# Cargador_RasPi3HAT_CamSlot_v1_0.net
KiCad netlist of a schematic drawn in EAGLE
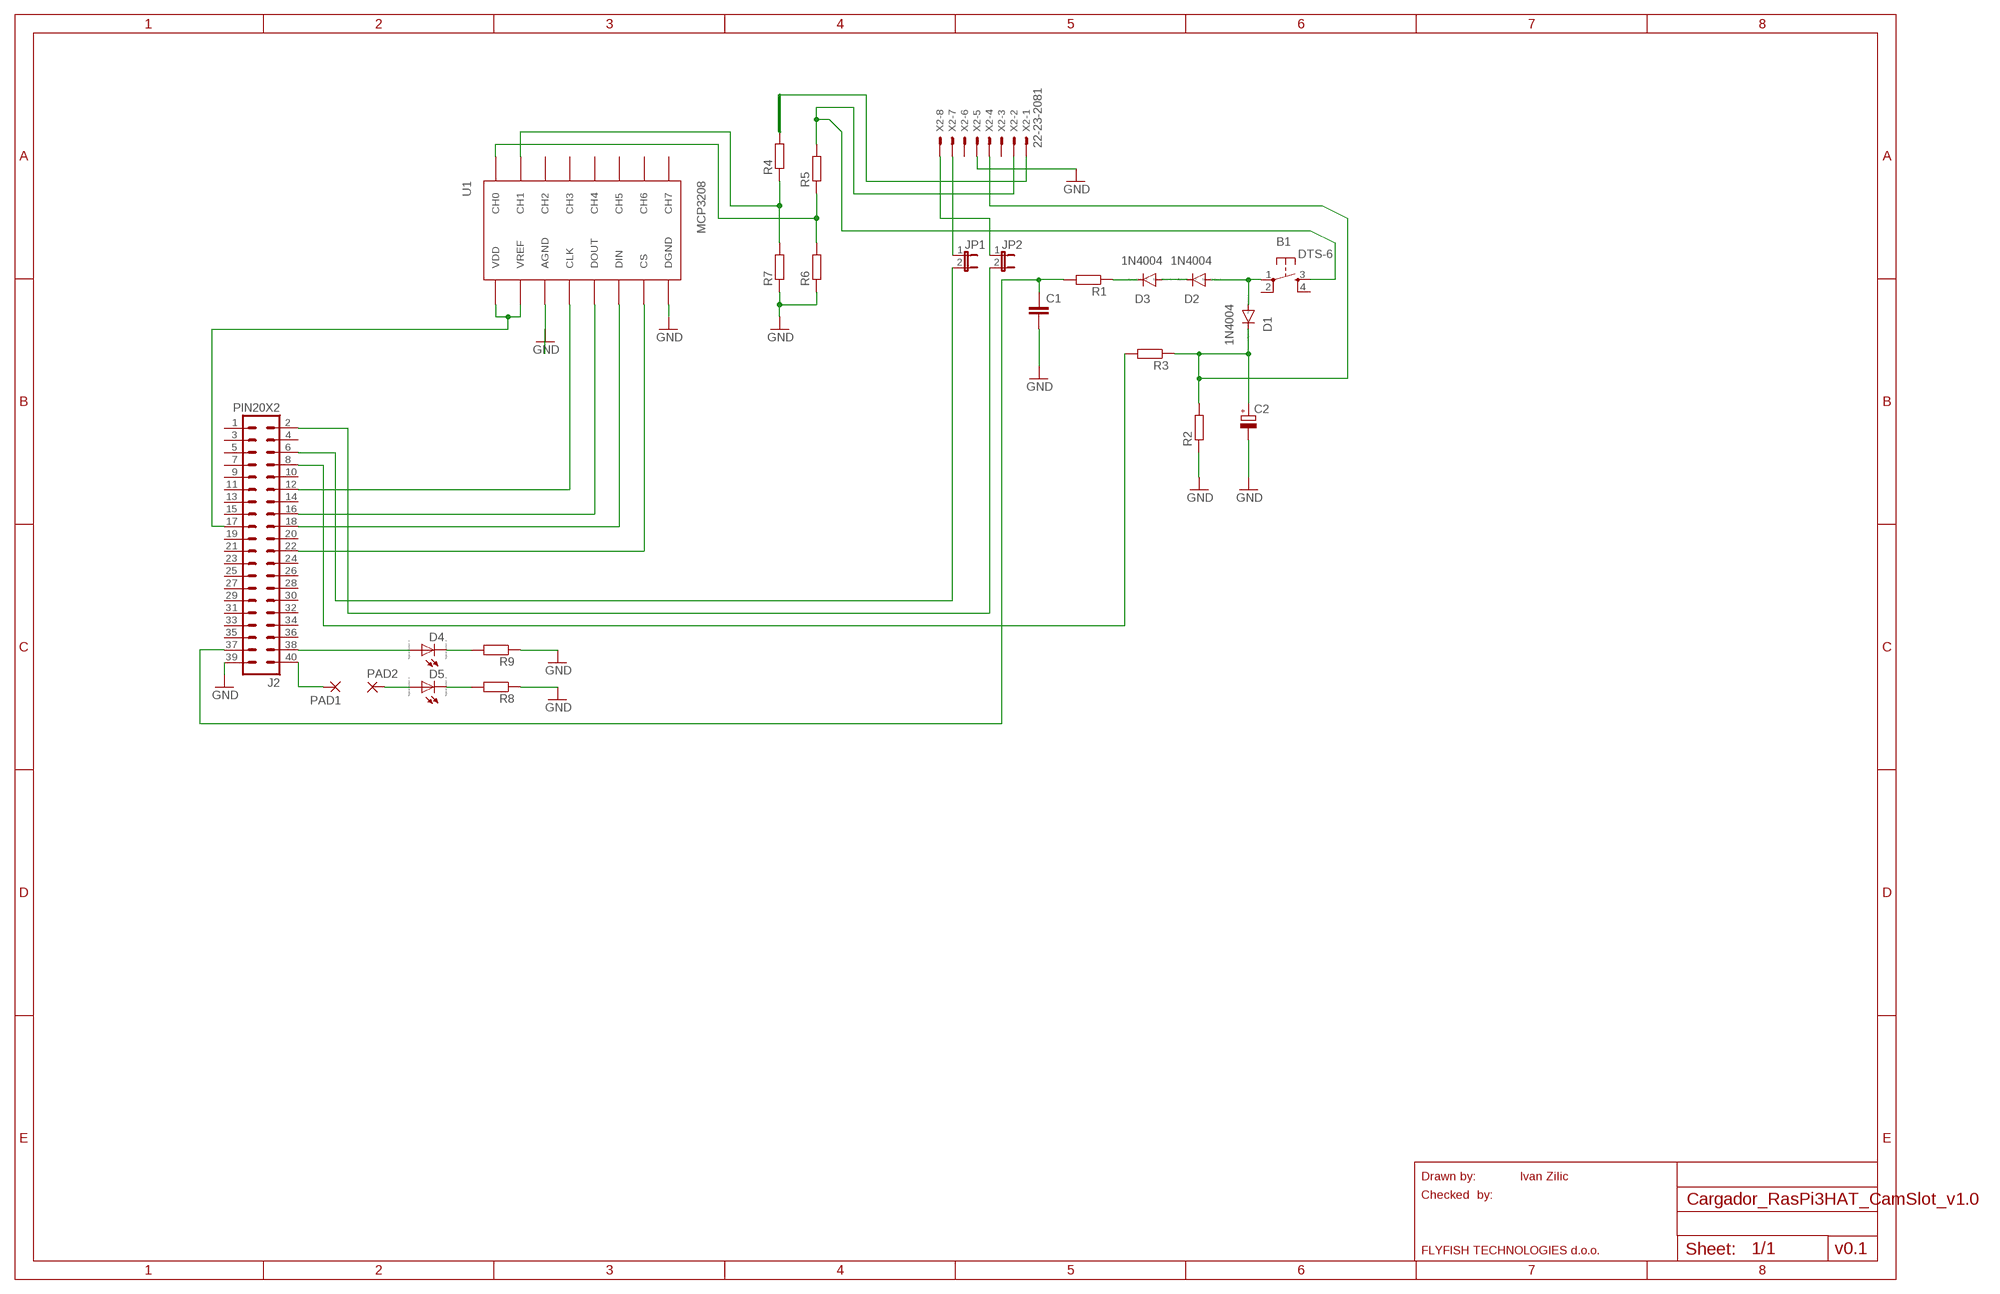
[diagram p0: schematic, sheet 1]

(export (version "E")
  (design (tool "Eeschema 10.0.6"))
  (components
    (comp (ref "B1")
      (value "DTS-6")
      (footprint "eagle-import:DTS-6")
      (libsource (lib "eagle-import") (part "DTS-6"))
    )
    (comp (ref "C1")
      (value "C2.5/2")
      (footprint "eagle-import:C2.5-2")
      (libsource (lib "eagle-import") (part "C2.5/2"))
    )
    (comp (ref "C2")
      (value "CPOL-EUE5-4")
      (footprint "eagle-import:E5-4")
      (libsource (lib "eagle-import") (part "CPOL-EUE5-4"))
    )
    (comp (ref "D1")
      (value "1N4004")
      (footprint "eagle-import:DO41-10")
      (libsource (lib "eagle-import") (part "1N4004"))
    )
    (comp (ref "D2")
      (value "1N4004")
      (footprint "eagle-import:DO41-10")
      (libsource (lib "eagle-import") (part "1N4004"))
    )
    (comp (ref "D3")
      (value "1N4004")
      (footprint "eagle-import:DO41-10")
      (libsource (lib "eagle-import") (part "1N4004"))
    )
    (comp (ref "D4")
      (value "LED_ELD260")
      (footprint "eagle-import:LED_LD260")
      (libsource (lib "eagle-import") (part "LED_ELD260"))
    )
    (comp (ref "D5")
      (value "LED_ELD260")
      (footprint "eagle-import:LED_LD260")
      (libsource (lib "eagle-import") (part "LED_ELD260"))
    )
    (comp (ref "J2")
      (value "PIN20X2")
      (footprint "eagle-import:PIN_20X2")
      (libsource (lib "eagle-import") (part "PIN20X2"))
    )
    (comp (ref "JP1")
      (value "JP1E")
      (footprint "eagle-import:JP1")
      (libsource (lib "eagle-import") (part "JP1E"))
    )
    (comp (ref "JP2")
      (value "JP1E")
      (footprint "eagle-import:JP1")
      (libsource (lib "eagle-import") (part "JP1E"))
    )
    (comp (ref "PAD1")
      (value "2,15/1,0")
      (footprint "eagle-import:2,15_1,0")
      (libsource (lib "eagle-import") (part "2,15/1,0"))
    )
    (comp (ref "PAD2")
      (value "2,15/1,0")
      (footprint "eagle-import:2,15_1,0")
      (libsource (lib "eagle-import") (part "2,15/1,0"))
    )
    (comp (ref "R1")
      (value "R-EU_0207/10")
      (footprint "eagle-import:0207_10")
      (libsource (lib "eagle-import") (part "R-EU_0207/10"))
    )
    (comp (ref "R2")
      (value "R-EU_0207/10")
      (footprint "eagle-import:0207_10")
      (libsource (lib "eagle-import") (part "R-EU_0207/10"))
    )
    (comp (ref "R3")
      (value "R-EU_0207/10")
      (footprint "eagle-import:0207_10")
      (libsource (lib "eagle-import") (part "R-EU_0207/10"))
    )
    (comp (ref "R4")
      (value "R-EU_0207/10")
      (footprint "eagle-import:0207_10")
      (libsource (lib "eagle-import") (part "R-EU_0207/10"))
    )
    (comp (ref "R5")
      (value "R-EU_0207/10")
      (footprint "eagle-import:0207_10")
      (libsource (lib "eagle-import") (part "R-EU_0207/10"))
    )
    (comp (ref "R6")
      (value "R-EU_0207/10")
      (footprint "eagle-import:0207_10")
      (libsource (lib "eagle-import") (part "R-EU_0207/10"))
    )
    (comp (ref "R7")
      (value "R-EU_0207/10")
      (footprint "eagle-import:0207_10")
      (libsource (lib "eagle-import") (part "R-EU_0207/10"))
    )
    (comp (ref "R8")
      (value "R-EU_0207/10")
      (footprint "eagle-import:0207_10")
      (libsource (lib "eagle-import") (part "R-EU_0207/10"))
    )
    (comp (ref "R9")
      (value "R-EU_0207/10")
      (footprint "eagle-import:0207_10")
      (libsource (lib "eagle-import") (part "R-EU_0207/10"))
    )
    (comp (ref "U1")
      (value "MCP3208")
      (footprint "eagle-import:DIL16")
      (libsource (lib "eagle-import") (part "MCP3208"))
    )
    (comp (ref "X2")
      (value "22-23-2081")
      (footprint "eagle-import:22-23-2081")
      (fields (field (name "MF") "MOLEX"))
      (libsource (lib "eagle-import") (part "22-23-2081"))
    )
  )
  (nets
    (net (code "1") (name "GND") (class "Default")
      (node (ref "C1") (pin "2") (pinfunction "2_2") (pintype "passive"))
      (node (ref "C2") (pin "-") (pinfunction "-_-") (pintype "passive"))
      (node (ref "J2") (pin "39") (pinfunction "39_39") (pintype "passive"))
      (node (ref "R2") (pin "1") (pinfunction "1_1") (pintype "passive"))
      (node (ref "R6") (pin "1") (pinfunction "1_1") (pintype "passive"))
      (node (ref "R7") (pin "1") (pinfunction "1_1") (pintype "passive"))
      (node (ref "R8") (pin "1") (pinfunction "1_1") (pintype "passive"))
      (node (ref "R9") (pin "1") (pinfunction "1_1") (pintype "passive"))
      (node (ref "U1") (pin "AGND") (pinfunction "AGND_AGND") (pintype "power_in"))
      (node (ref "U1") (pin "DGND") (pinfunction "DGND_DGND") (pintype "power_in"))
      (node (ref "X2") (pin "5") (pinfunction "S_5") (pintype "passive"))
    )
    (net (code "2") (name "Net-(B1-Pad1)") (class "Default")
      (node (ref "B1") (pin "1") (pinfunction "1_1") (pintype "passive"))
      (node (ref "D1") (pin "A") (pinfunction "A_A") (pintype "passive"))
      (node (ref "D2") (pin "A") (pinfunction "A_A") (pintype "passive"))
    )
    (net (code "3") (name "Net-(C1-Pad1)") (class "Default")
      (node (ref "C1") (pin "1") (pinfunction "1_1") (pintype "passive"))
      (node (ref "J2") (pin "37") (pinfunction "37_37") (pintype "passive"))
      (node (ref "R1") (pin "2") (pinfunction "2_2") (pintype "passive"))
    )
    (net (code "4") (name "Net-(D2-PadC)") (class "Default")
      (node (ref "D2") (pin "C") (pinfunction "C_C") (pintype "passive"))
      (node (ref "D3") (pin "A") (pinfunction "A_A") (pintype "passive"))
    )
    (net (code "5") (name "Net-(D3-PadC)") (class "Default")
      (node (ref "D3") (pin "C") (pinfunction "C_C") (pintype "passive"))
      (node (ref "R1") (pin "1") (pinfunction "1_1") (pintype "passive"))
    )
    (net (code "6") (name "Net-(D4-C)") (class "Default")
      (node (ref "D4") (pin "K") (pinfunction "C_K") (pintype "passive"))
      (node (ref "R9") (pin "2") (pinfunction "2_2") (pintype "passive"))
    )
    (net (code "7") (name "Net-(D4-PadA)") (class "Default")
      (node (ref "D4") (pin "A") (pinfunction "A_A") (pintype "passive"))
      (node (ref "J2") (pin "38") (pinfunction "38_38") (pintype "passive"))
    )
    (net (code "8") (name "Net-(D5-C)") (class "Default")
      (node (ref "D5") (pin "K") (pinfunction "C_K") (pintype "passive"))
      (node (ref "R8") (pin "2") (pinfunction "2_2") (pintype "passive"))
    )
    (net (code "9") (name "Net-(J2-Pad2)") (class "Default")
      (node (ref "J2") (pin "2") (pinfunction "2_2") (pintype "passive"))
      (node (ref "JP2") (pin "2") (pinfunction "2_2") (pintype "passive"))
    )
    (net (code "10") (name "Net-(J2-Pad6)") (class "Default")
      (node (ref "J2") (pin "6") (pinfunction "6_6") (pintype "passive"))
      (node (ref "JP1") (pin "2") (pinfunction "2_2") (pintype "passive"))
    )
    (net (code "11") (name "Net-(J2-Pad8)") (class "Default")
      (node (ref "J2") (pin "8") (pinfunction "8_8") (pintype "passive"))
      (node (ref "R3") (pin "2") (pinfunction "2_2") (pintype "passive"))
    )
    (net (code "12") (name "Net-(J2-Pad12)") (class "Default")
      (node (ref "J2") (pin "12") (pinfunction "12_12") (pintype "passive"))
      (node (ref "U1") (pin "CLK") (pinfunction "CLK_CLK") (pintype "input"))
    )
    (net (code "13") (name "Net-(J2-Pad16)") (class "Default")
      (node (ref "J2") (pin "16") (pinfunction "16_16") (pintype "passive"))
      (node (ref "U1") (pin "DOUT") (pinfunction "DOUT_DOUT") (pintype "output"))
    )
    (net (code "14") (name "Net-(J2-Pad17)") (class "Default")
      (node (ref "J2") (pin "17") (pinfunction "17_17") (pintype "passive"))
      (node (ref "U1") (pin "VDD") (pinfunction "VDD_VDD") (pintype "power_in"))
      (node (ref "U1") (pin "VREF") (pinfunction "VREF_VREF") (pintype "input"))
    )
    (net (code "15") (name "Net-(J2-Pad18)") (class "Default")
      (node (ref "J2") (pin "18") (pinfunction "18_18") (pintype "passive"))
      (node (ref "U1") (pin "DIN") (pinfunction "DIN_DIN") (pintype "input"))
    )
    (net (code "16") (name "Net-(J2-Pad22)") (class "Default")
      (node (ref "J2") (pin "22") (pinfunction "22_22") (pintype "passive"))
      (node (ref "U1") (pin "CS") (pinfunction "CS_CS") (pintype "input"))
    )
    (net (code "17") (name "Net-(PAD1-P)") (class "Default")
      (node (ref "J2") (pin "40") (pinfunction "40_40") (pintype "passive"))
      (node (ref "PAD1") (pin "1") (pinfunction "P_1") (pintype "passive"))
    )
    (net (code "18") (name "Net-(PAD2-P)") (class "Default")
      (node (ref "D5") (pin "A") (pinfunction "A_A") (pintype "passive"))
      (node (ref "PAD2") (pin "1") (pinfunction "P_1") (pintype "passive"))
    )
    (net (code "19") (name "Net-(R4-Pad1)") (class "Default")
      (node (ref "R4") (pin "1") (pinfunction "1_1") (pintype "passive"))
      (node (ref "R7") (pin "2") (pinfunction "2_2") (pintype "passive"))
      (node (ref "U1") (pin "CH1") (pinfunction "CH1_CH1") (pintype "input"))
    )
    (net (code "20") (name "Net-(R5-Pad1)") (class "Default")
      (node (ref "R5") (pin "1") (pinfunction "1_1") (pintype "passive"))
      (node (ref "R6") (pin "2") (pinfunction "2_2") (pintype "passive"))
      (node (ref "U1") (pin "CH0") (pinfunction "CH0_CH0") (pintype "input"))
    )
    (net (code "21") (name "Net-(X2A-S)") (class "Default")
      (node (ref "R4") (pin "2") (pinfunction "2_2") (pintype "passive"))
      (node (ref "X2") (pin "1") (pinfunction "S_1") (pintype "passive"))
    )
    (net (code "22") (name "Net-(X2B-S)") (class "Default")
      (node (ref "B1") (pin "3") (pinfunction "3_3") (pintype "passive"))
      (node (ref "R5") (pin "2") (pinfunction "2_2") (pintype "passive"))
      (node (ref "X2") (pin "2") (pinfunction "S_2") (pintype "passive"))
    )
    (net (code "23") (name "Net-(X2D-S)") (class "Default")
      (node (ref "C2") (pin "+") (pinfunction "+_+") (pintype "passive"))
      (node (ref "D1") (pin "C") (pinfunction "C_C") (pintype "passive"))
      (node (ref "R2") (pin "2") (pinfunction "2_2") (pintype "passive"))
      (node (ref "R3") (pin "1") (pinfunction "1_1") (pintype "passive"))
      (node (ref "X2") (pin "4") (pinfunction "S_4") (pintype "passive"))
    )
    (net (code "24") (name "Net-(X2G-S)") (class "Default")
      (node (ref "JP1") (pin "1") (pinfunction "1_1") (pintype "passive"))
      (node (ref "X2") (pin "7") (pinfunction "S_7") (pintype "passive"))
    )
    (net (code "25") (name "Net-(X2H-S)") (class "Default")
      (node (ref "JP2") (pin "1") (pinfunction "1_1") (pintype "passive"))
      (node (ref "X2") (pin "8") (pinfunction "S_8") (pintype "passive"))
    )
    (net (code "26") (name "unconnected-(B1-Pad2)") (class "Default")
      (node (ref "B1") (pin "2") (pinfunction "2_2") (pintype "passive"))
    )
    (net (code "27") (name "unconnected-(B1-Pad4)") (class "Default")
      (node (ref "B1") (pin "4") (pinfunction "4_4") (pintype "passive"))
    )
    (net (code "28") (name "unconnected-(J2-Pad1)") (class "Default")
      (node (ref "J2") (pin "1") (pinfunction "1_1") (pintype "passive"))
    )
    (net (code "29") (name "unconnected-(J2-Pad3)") (class "Default")
      (node (ref "J2") (pin "3") (pinfunction "3_3") (pintype "passive"))
    )
    (net (code "30") (name "unconnected-(J2-Pad4)") (class "Default")
      (node (ref "J2") (pin "4") (pinfunction "4_4") (pintype "passive"))
    )
    (net (code "31") (name "unconnected-(J2-Pad5)") (class "Default")
      (node (ref "J2") (pin "5") (pinfunction "5_5") (pintype "passive"))
    )
    (net (code "32") (name "unconnected-(J2-Pad7)") (class "Default")
      (node (ref "J2") (pin "7") (pinfunction "7_7") (pintype "passive"))
    )
    (net (code "33") (name "unconnected-(J2-Pad9)") (class "Default")
      (node (ref "J2") (pin "9") (pinfunction "9_9") (pintype "passive"))
    )
    (net (code "34") (name "unconnected-(J2-Pad10)") (class "Default")
      (node (ref "J2") (pin "10") (pinfunction "10_10") (pintype "passive"))
    )
    (net (code "35") (name "unconnected-(J2-Pad11)") (class "Default")
      (node (ref "J2") (pin "11") (pinfunction "11_11") (pintype "passive"))
    )
    (net (code "36") (name "unconnected-(J2-Pad13)") (class "Default")
      (node (ref "J2") (pin "13") (pinfunction "13_13") (pintype "passive"))
    )
    (net (code "37") (name "unconnected-(J2-Pad14)") (class "Default")
      (node (ref "J2") (pin "14") (pinfunction "14_14") (pintype "passive"))
    )
    (net (code "38") (name "unconnected-(J2-Pad15)") (class "Default")
      (node (ref "J2") (pin "15") (pinfunction "15_15") (pintype "passive"))
    )
    (net (code "39") (name "unconnected-(J2-Pad19)") (class "Default")
      (node (ref "J2") (pin "19") (pinfunction "19_19") (pintype "passive"))
    )
    (net (code "40") (name "unconnected-(J2-Pad20)") (class "Default")
      (node (ref "J2") (pin "20") (pinfunction "20_20") (pintype "passive"))
    )
    (net (code "41") (name "unconnected-(J2-Pad21)") (class "Default")
      (node (ref "J2") (pin "21") (pinfunction "21_21") (pintype "passive"))
    )
    (net (code "42") (name "unconnected-(J2-Pad23)") (class "Default")
      (node (ref "J2") (pin "23") (pinfunction "23_23") (pintype "passive"))
    )
    (net (code "43") (name "unconnected-(J2-Pad24)") (class "Default")
      (node (ref "J2") (pin "24") (pinfunction "24_24") (pintype "passive"))
    )
    (net (code "44") (name "unconnected-(J2-Pad25)") (class "Default")
      (node (ref "J2") (pin "25") (pinfunction "25_25") (pintype "passive"))
    )
    (net (code "45") (name "unconnected-(J2-Pad26)") (class "Default")
      (node (ref "J2") (pin "26") (pinfunction "26_26") (pintype "passive"))
    )
    (net (code "46") (name "unconnected-(J2-Pad27)") (class "Default")
      (node (ref "J2") (pin "27") (pinfunction "27_27") (pintype "passive"))
    )
    (net (code "47") (name "unconnected-(J2-Pad28)") (class "Default")
      (node (ref "J2") (pin "28") (pinfunction "28_28") (pintype "passive"))
    )
    (net (code "48") (name "unconnected-(J2-Pad29)") (class "Default")
      (node (ref "J2") (pin "29") (pinfunction "29_29") (pintype "passive"))
    )
    (net (code "49") (name "unconnected-(J2-Pad30)") (class "Default")
      (node (ref "J2") (pin "30") (pinfunction "30_30") (pintype "passive"))
    )
    (net (code "50") (name "unconnected-(J2-Pad31)") (class "Default")
      (node (ref "J2") (pin "31") (pinfunction "31_31") (pintype "passive"))
    )
    (net (code "51") (name "unconnected-(J2-Pad32)") (class "Default")
      (node (ref "J2") (pin "32") (pinfunction "32_32") (pintype "passive"))
    )
    (net (code "52") (name "unconnected-(J2-Pad33)") (class "Default")
      (node (ref "J2") (pin "33") (pinfunction "33_33") (pintype "passive"))
    )
    (net (code "53") (name "unconnected-(J2-Pad34)") (class "Default")
      (node (ref "J2") (pin "34") (pinfunction "34_34") (pintype "passive"))
    )
    (net (code "54") (name "unconnected-(J2-Pad35)") (class "Default")
      (node (ref "J2") (pin "35") (pinfunction "35_35") (pintype "passive"))
    )
    (net (code "55") (name "unconnected-(J2-Pad36)") (class "Default")
      (node (ref "J2") (pin "36") (pinfunction "36_36") (pintype "passive"))
    )
    (net (code "56") (name "unconnected-(U1-PadCH2)") (class "Default")
      (node (ref "U1") (pin "CH2") (pinfunction "CH2_CH2") (pintype "input"))
    )
    (net (code "57") (name "unconnected-(U1-PadCH3)") (class "Default")
      (node (ref "U1") (pin "CH3") (pinfunction "CH3_CH3") (pintype "input"))
    )
    (net (code "58") (name "unconnected-(U1-PadCH4)") (class "Default")
      (node (ref "U1") (pin "CH4") (pinfunction "CH4_CH4") (pintype "input"))
    )
    (net (code "59") (name "unconnected-(U1-PadCH5)") (class "Default")
      (node (ref "U1") (pin "CH5") (pinfunction "CH5_CH5") (pintype "input"))
    )
    (net (code "60") (name "unconnected-(U1-PadCH6)") (class "Default")
      (node (ref "U1") (pin "CH6") (pinfunction "CH6_CH6") (pintype "input"))
    )
    (net (code "61") (name "unconnected-(U1-PadCH7)") (class "Default")
      (node (ref "U1") (pin "CH7") (pinfunction "CH7_CH7") (pintype "input"))
    )
    (net (code "62") (name "unconnected-(X2C-S-Pad3)") (class "Default")
      (node (ref "X2") (pin "3") (pinfunction "S_3") (pintype "passive"))
    )
    (net (code "63") (name "unconnected-(X2F-S-Pad6)") (class "Default")
      (node (ref "X2") (pin "6") (pinfunction "S_6") (pintype "passive"))
    )
  )
)
